# vest_belter_borox.net
KiCad netlist of a schematic drawn in EAGLE
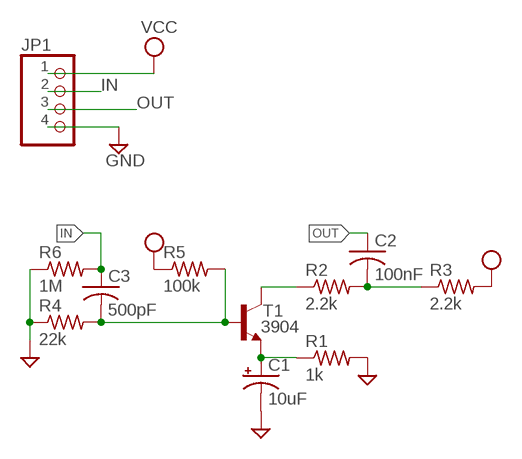
[diagram p0: schematic, sheet 1]

(export (version "E")
  (design (tool "Eeschema 10.0.6"))
  (components
    (comp (ref "C1")
      (value "10uF")
      (footprint "eagle-import:CAPMP3216X180N")
      (libsource (lib "eagle-import") (part "C-POL-USTANTALUM-1206(3216-METRIC)_"))
    )
    (comp (ref "C2")
      (value "100nF")
      (footprint "eagle-import:C0603")
      (libsource (lib "eagle-import") (part "C-USC0603"))
    )
    (comp (ref "C3")
      (value "500pF")
      (footprint "eagle-import:C0603")
      (libsource (lib "eagle-import") (part "C-USC0603"))
    )
    (comp (ref "JP1")
      (value "PINHD-1X4")
      (footprint "eagle-import:1X04")
      (libsource (lib "eagle-import") (part "PINHD-1X4"))
    )
    (comp (ref "R1")
      (value "1k")
      (footprint "eagle-import:R0603")
      (libsource (lib "eagle-import") (part "R-US_R0603"))
    )
    (comp (ref "R2")
      (value "2.2k")
      (footprint "eagle-import:R0603")
      (libsource (lib "eagle-import") (part "R-US_R0603"))
    )
    (comp (ref "R3")
      (value "2.2k")
      (footprint "eagle-import:R0603")
      (libsource (lib "eagle-import") (part "R-US_R0603"))
    )
    (comp (ref "R4")
      (value "22k")
      (footprint "eagle-import:R0603")
      (libsource (lib "eagle-import") (part "R-US_R0603"))
    )
    (comp (ref "R5")
      (value "100k")
      (footprint "eagle-import:R0603")
      (libsource (lib "eagle-import") (part "R-US_R0603"))
    )
    (comp (ref "R6")
      (value "1M")
      (footprint "eagle-import:R0603")
      (libsource (lib "eagle-import") (part "R-US_R0603"))
    )
    (comp (ref "T1")
      (value "3904")
      (footprint "eagle-import:SOT23-BEC")
      (libsource (lib "eagle-import") (part "-NPN-SOT23-BECMMBT3904LT1"))
    )
  )
  (nets
    (net (code "1") (name "GND") (class "Default")
      (node (ref "C1") (pin "2") (pinfunction "-_2") (pintype "passive"))
      (node (ref "JP1") (pin "4") (pinfunction "4_4") (pintype "passive"))
      (node (ref "R1") (pin "2") (pinfunction "2_2") (pintype "passive"))
      (node (ref "R4") (pin "1") (pinfunction "1_1") (pintype "passive"))
      (node (ref "R6") (pin "1") (pinfunction "1_1") (pintype "passive"))
    )
    (net (code "2") (name "IN") (class "Default")
      (node (ref "C3") (pin "1") (pinfunction "1_1") (pintype "passive"))
      (node (ref "JP1") (pin "2") (pinfunction "2_2") (pintype "passive"))
      (node (ref "R6") (pin "2") (pinfunction "2_2") (pintype "passive"))
    )
    (net (code "3") (name "Net-(C1-+)") (class "Default")
      (node (ref "C1") (pin "1") (pinfunction "+_1") (pintype "passive"))
      (node (ref "R1") (pin "1") (pinfunction "1_1") (pintype "passive"))
      (node (ref "T1") (pin "E") (pinfunction "E_E") (pintype "passive"))
    )
    (net (code "4") (name "Net-(C2-Pad2)") (class "Default")
      (node (ref "C2") (pin "2") (pinfunction "2_2") (pintype "passive"))
      (node (ref "R2") (pin "2") (pinfunction "2_2") (pintype "passive"))
      (node (ref "R3") (pin "1") (pinfunction "1_1") (pintype "passive"))
    )
    (net (code "5") (name "Net-(C3-Pad2)") (class "Default")
      (node (ref "C3") (pin "2") (pinfunction "2_2") (pintype "passive"))
      (node (ref "R4") (pin "2") (pinfunction "2_2") (pintype "passive"))
      (node (ref "R5") (pin "2") (pinfunction "2_2") (pintype "passive"))
      (node (ref "T1") (pin "B") (pinfunction "B_B") (pintype "passive"))
    )
    (net (code "6") (name "Net-(R2-Pad1)") (class "Default")
      (node (ref "R2") (pin "1") (pinfunction "1_1") (pintype "passive"))
      (node (ref "T1") (pin "C") (pinfunction "C_C") (pintype "passive"))
    )
    (net (code "7") (name "OUT") (class "Default")
      (node (ref "C2") (pin "1") (pinfunction "1_1") (pintype "passive"))
      (node (ref "JP1") (pin "3") (pinfunction "3_3") (pintype "passive"))
    )
    (net (code "8") (name "VCC") (class "Default")
      (node (ref "JP1") (pin "1") (pinfunction "1_1") (pintype "passive"))
      (node (ref "R3") (pin "2") (pinfunction "2_2") (pintype "passive"))
      (node (ref "R5") (pin "1") (pinfunction "1_1") (pintype "passive"))
    )
  )
)
